# 12_FPGA_MONITOR.net
KiCad netlist of a schematic drawn in Altium Designer
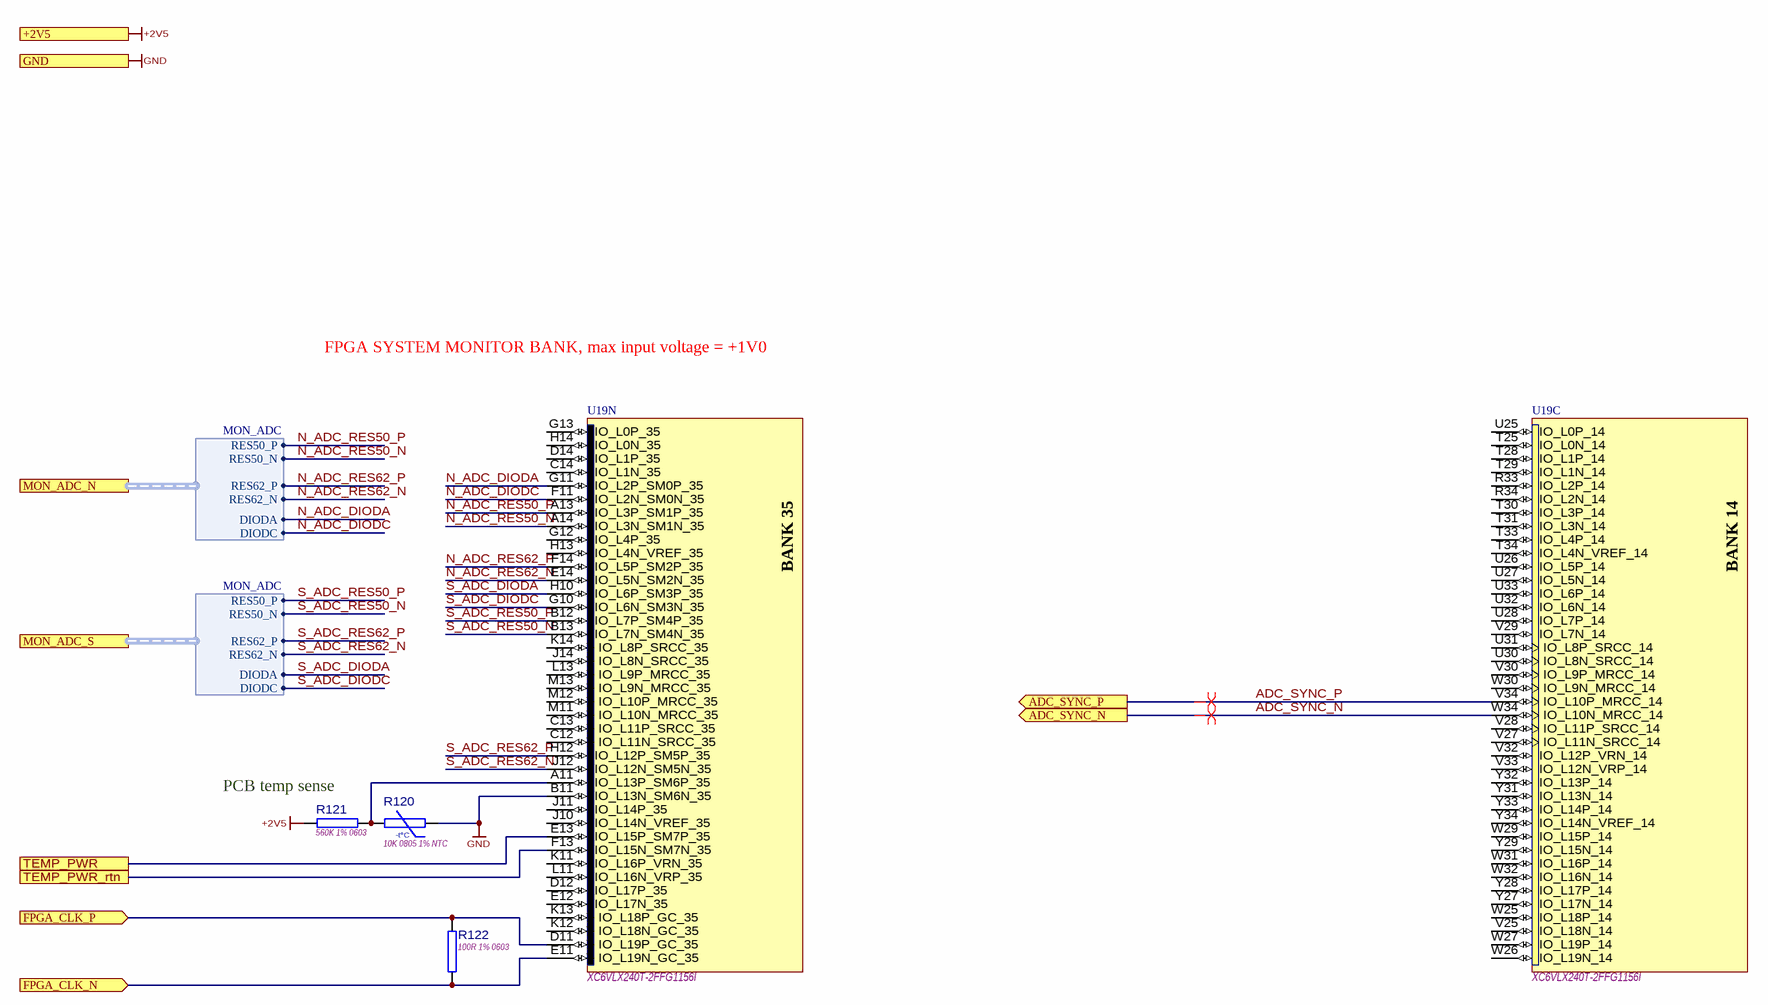
[diagram p0: [12] FPGA_MONITOR.SchDoc]

(export (version "E")
  (design (tool "Eeschema 10.0.6"))
  (components
    (comp (ref "R120")
      (value "10K 0805 1% NTC")
      (footprint "RESC2012N")
      (description "10K NTC resistor 1%  0805 (2012 metric)")
      (fields (field (name "PARTNUMBER") "NTCS0805E3103FLT"))
      (libsource (lib "Omnisys Vault") (part "RES-2PIN-NTC"))
    )
    (comp (ref "R121")
      (value "560K 1% 0603")
      (footprint "RESC1608N")
      (description "Thick film Chip Resistor, 0603/1608")
      (fields (field (name "POWER") "100mW") (field (name "TOLERANCE") "1%"))
      (libsource (lib "Omnisys Vault") (part "RES-2PIN"))
    )
    (comp (ref "R122")
      (value "100R 1% 0603")
      (footprint "RESC1608N")
      (description "Thick film Chip Resistor, 0603/1608")
      (fields (field (name "POWER") "100mW") (field (name "TOLERANCE") "1%"))
      (libsource (lib "Omnisys Vault") (part "RES-2PIN"))
    )
    (comp (ref "U19")
      (value "XC6VLX240T-2FFG1156I")
      (footprint "FFG1156")
      (description "FPGA Virtex-6 LXT Family 241152 Cells 40nm (CMOS) Technology 1V 1156-Pin FCBGA")
      (libsource (lib "Omnisys Vault") (part "FPGA-XVR6-XC6VXXXXXT-GA1156"))
    )
  )
  (nets
    (net (code "2") (name "+2V5") (class "Default")
      (node (ref "R121") (pin "1") (pinfunction "1_1") (pintype "passive"))
    )
    (net (code "3") (name "/ADC_SYNC_N") (class "Default")
      (node (ref "U19") (pin "W34") (pinfunction "IO_L10N_MRCC_14_W34") (pintype "bidirectional"))
    )
    (net (code "4") (name "/ADC_SYNC_P") (class "Default")
      (node (ref "U19") (pin "V34") (pinfunction "IO_L10P_MRCC_14_V34") (pintype "bidirectional"))
    )
    (net (code "5") (name "/FPGA_CLK_N") (class "Default")
      (node (ref "R122") (pin "1") (pinfunction "1_1") (pintype "passive"))
      (node (ref "U19") (pin "E11") (pinfunction "IO_L19N_GC_35_E11") (pintype "bidirectional"))
    )
    (net (code "6") (name "/FPGA_CLK_P") (class "Default")
      (node (ref "R122") (pin "2") (pinfunction "2_2") (pintype "passive"))
      (node (ref "U19") (pin "D11") (pinfunction "IO_L19P_GC_35_D11") (pintype "bidirectional"))
    )
    (net (code "7") (name "/N_ADC_DIODA") (class "Default")
      (node (ref "U19") (pin "G11") (pinfunction "IO_L2P_SM0P_35_G11") (pintype "bidirectional"))
    )
    (net (code "8") (name "/N_ADC_DIODC") (class "Default")
      (node (ref "U19") (pin "F11") (pinfunction "IO_L2N_SM0N_35_F11") (pintype "bidirectional"))
    )
    (net (code "9") (name "/N_ADC_RES50_N") (class "Default")
      (node (ref "U19") (pin "A14") (pinfunction "IO_L3N_SM1N_35_A14") (pintype "bidirectional"))
    )
    (net (code "10") (name "/N_ADC_RES50_P") (class "Default")
      (node (ref "U19") (pin "A13") (pinfunction "IO_L3P_SM1P_35_A13") (pintype "bidirectional"))
    )
    (net (code "11") (name "/N_ADC_RES62_N") (class "Default")
      (node (ref "U19") (pin "E14") (pinfunction "IO_L5N_SM2N_35_E14") (pintype "bidirectional"))
    )
    (net (code "12") (name "/N_ADC_RES62_P") (class "Default")
      (node (ref "U19") (pin "F14") (pinfunction "IO_L5P_SM2P_35_F14") (pintype "bidirectional"))
    )
    (net (code "13") (name "/S_ADC_DIODA") (class "Default")
      (node (ref "U19") (pin "H10") (pinfunction "IO_L6P_SM3P_35_H10") (pintype "bidirectional"))
    )
    (net (code "14") (name "/S_ADC_DIODC") (class "Default")
      (node (ref "U19") (pin "G10") (pinfunction "IO_L6N_SM3N_35_G10") (pintype "bidirectional"))
    )
    (net (code "15") (name "/S_ADC_RES50_N") (class "Default")
      (node (ref "U19") (pin "B13") (pinfunction "IO_L7N_SM4N_35_B13") (pintype "bidirectional"))
    )
    (net (code "16") (name "/S_ADC_RES50_P") (class "Default")
      (node (ref "U19") (pin "B12") (pinfunction "IO_L7P_SM4P_35_B12") (pintype "bidirectional"))
    )
    (net (code "17") (name "/S_ADC_RES62_N") (class "Default")
      (node (ref "U19") (pin "J12") (pinfunction "IO_L12N_SM5N_35_J12") (pintype "bidirectional"))
    )
    (net (code "18") (name "/S_ADC_RES62_P") (class "Default")
      (node (ref "U19") (pin "H12") (pinfunction "IO_L12P_SM5P_35_H12") (pintype "bidirectional"))
    )
    (net (code "19") (name "/TEMP_PWR") (class "Default")
      (node (ref "U19") (pin "E13") (pinfunction "IO_L15P_SM7P_35_E13") (pintype "bidirectional"))
    )
    (net (code "20") (name "/TEMP_PWR_rtn") (class "Default")
      (node (ref "U19") (pin "F13") (pinfunction "IO_L15N_SM7N_35_F13") (pintype "bidirectional"))
    )
    (net (code "22") (name "GND") (class "Default")
      (node (ref "R120") (pin "1") (pinfunction "1_1") (pintype "passive"))
      (node (ref "U19") (pin "B11") (pinfunction "IO_L13N_SM6N_35_B11") (pintype "bidirectional"))
    )
    (net (code "23") (name "Net-(U19N-IO_L13P_SM6P_35)") (class "Default")
      (node (ref "R120") (pin "2") (pinfunction "2_2") (pintype "passive"))
      (node (ref "R121") (pin "2") (pinfunction "2_2") (pintype "passive"))
      (node (ref "U19") (pin "A11") (pinfunction "IO_L13P_SM6P_35_A11") (pintype "bidirectional"))
    )
    (net (code "24") (name "unconnected-(U19C-IO_L0N_14-PadT25)") (class "Default")
      (node (ref "U19") (pin "T25") (pinfunction "IO_L0N_14_T25") (pintype "bidirectional"))
    )
    (net (code "25") (name "unconnected-(U19C-IO_L0P_14-PadU25)") (class "Default")
      (node (ref "U19") (pin "U25") (pinfunction "IO_L0P_14_U25") (pintype "bidirectional"))
    )
    (net (code "26") (name "unconnected-(U19C-IO_L1N_14-PadT29)") (class "Default")
      (node (ref "U19") (pin "T29") (pinfunction "IO_L1N_14_T29") (pintype "bidirectional"))
    )
    (net (code "27") (name "unconnected-(U19C-IO_L1P_14-PadT28)") (class "Default")
      (node (ref "U19") (pin "T28") (pinfunction "IO_L1P_14_T28") (pintype "bidirectional"))
    )
    (net (code "28") (name "unconnected-(U19C-IO_L2N_14-PadR34)") (class "Default")
      (node (ref "U19") (pin "R34") (pinfunction "IO_L2N_14_R34") (pintype "bidirectional"))
    )
    (net (code "29") (name "unconnected-(U19C-IO_L2P_14-PadR33)") (class "Default")
      (node (ref "U19") (pin "R33") (pinfunction "IO_L2P_14_R33") (pintype "bidirectional"))
    )
    (net (code "30") (name "unconnected-(U19C-IO_L3N_14-PadT31)") (class "Default")
      (node (ref "U19") (pin "T31") (pinfunction "IO_L3N_14_T31") (pintype "bidirectional"))
    )
    (net (code "31") (name "unconnected-(U19C-IO_L3P_14-PadT30)") (class "Default")
      (node (ref "U19") (pin "T30") (pinfunction "IO_L3P_14_T30") (pintype "bidirectional"))
    )
    (net (code "32") (name "unconnected-(U19C-IO_L4N_VREF_14-PadT34)") (class "Default")
      (node (ref "U19") (pin "T34") (pinfunction "IO_L4N_VREF_14_T34") (pintype "bidirectional"))
    )
    (net (code "33") (name "unconnected-(U19C-IO_L4P_14-PadT33)") (class "Default")
      (node (ref "U19") (pin "T33") (pinfunction "IO_L4P_14_T33") (pintype "bidirectional"))
    )
    (net (code "34") (name "unconnected-(U19C-IO_L5N_14-PadU27)") (class "Default")
      (node (ref "U19") (pin "U27") (pinfunction "IO_L5N_14_U27") (pintype "bidirectional"))
    )
    (net (code "35") (name "unconnected-(U19C-IO_L5P_14-PadU26)") (class "Default")
      (node (ref "U19") (pin "U26") (pinfunction "IO_L5P_14_U26") (pintype "bidirectional"))
    )
    (net (code "36") (name "unconnected-(U19C-IO_L6N_14-PadU32)") (class "Default")
      (node (ref "U19") (pin "U32") (pinfunction "IO_L6N_14_U32") (pintype "bidirectional"))
    )
    (net (code "37") (name "unconnected-(U19C-IO_L6P_14-PadU33)") (class "Default")
      (node (ref "U19") (pin "U33") (pinfunction "IO_L6P_14_U33") (pintype "bidirectional"))
    )
    (net (code "38") (name "unconnected-(U19C-IO_L7N_14-PadV29)") (class "Default")
      (node (ref "U19") (pin "V29") (pinfunction "IO_L7N_14_V29") (pintype "bidirectional"))
    )
    (net (code "39") (name "unconnected-(U19C-IO_L7P_14-PadU28)") (class "Default")
      (node (ref "U19") (pin "U28") (pinfunction "IO_L7P_14_U28") (pintype "bidirectional"))
    )
    (net (code "40") (name "unconnected-(U19C-IO_L8N_SRCC_14-PadU30)") (class "Default")
      (node (ref "U19") (pin "U30") (pinfunction "IO_L8N_SRCC_14_U30") (pintype "bidirectional"))
    )
    (net (code "41") (name "unconnected-(U19C-IO_L8P_SRCC_14-PadU31)") (class "Default")
      (node (ref "U19") (pin "U31") (pinfunction "IO_L8P_SRCC_14_U31") (pintype "bidirectional"))
    )
    (net (code "42") (name "unconnected-(U19C-IO_L9N_MRCC_14-PadW30)") (class "Default")
      (node (ref "U19") (pin "W30") (pinfunction "IO_L9N_MRCC_14_W30") (pintype "bidirectional"))
    )
    (net (code "43") (name "unconnected-(U19C-IO_L9P_MRCC_14-PadV30)") (class "Default")
      (node (ref "U19") (pin "V30") (pinfunction "IO_L9P_MRCC_14_V30") (pintype "bidirectional"))
    )
    (net (code "44") (name "unconnected-(U19C-IO_L11N_SRCC_14-PadV27)") (class "Default")
      (node (ref "U19") (pin "V27") (pinfunction "IO_L11N_SRCC_14_V27") (pintype "bidirectional"))
    )
    (net (code "45") (name "unconnected-(U19C-IO_L11P_SRCC_14-PadV28)") (class "Default")
      (node (ref "U19") (pin "V28") (pinfunction "IO_L11P_SRCC_14_V28") (pintype "bidirectional"))
    )
    (net (code "46") (name "unconnected-(U19C-IO_L12N_VRP_14-PadV33)") (class "Default")
      (node (ref "U19") (pin "V33") (pinfunction "IO_L12N_VRP_14_V33") (pintype "bidirectional"))
    )
    (net (code "47") (name "unconnected-(U19C-IO_L12P_VRN_14-PadV32)") (class "Default")
      (node (ref "U19") (pin "V32") (pinfunction "IO_L12P_VRN_14_V32") (pintype "bidirectional"))
    )
    (net (code "48") (name "unconnected-(U19C-IO_L13N_14-PadY31)") (class "Default")
      (node (ref "U19") (pin "Y31") (pinfunction "IO_L13N_14_Y31") (pintype "bidirectional"))
    )
    (net (code "49") (name "unconnected-(U19C-IO_L13P_14-PadY32)") (class "Default")
      (node (ref "U19") (pin "Y32") (pinfunction "IO_L13P_14_Y32") (pintype "bidirectional"))
    )
    (net (code "50") (name "unconnected-(U19C-IO_L14N_VREF_14-PadY34)") (class "Default")
      (node (ref "U19") (pin "Y34") (pinfunction "IO_L14N_VREF_14_Y34") (pintype "bidirectional"))
    )
    (net (code "51") (name "unconnected-(U19C-IO_L14P_14-PadY33)") (class "Default")
      (node (ref "U19") (pin "Y33") (pinfunction "IO_L14P_14_Y33") (pintype "bidirectional"))
    )
    (net (code "52") (name "unconnected-(U19C-IO_L15N_14-PadY29)") (class "Default")
      (node (ref "U19") (pin "Y29") (pinfunction "IO_L15N_14_Y29") (pintype "bidirectional"))
    )
    (net (code "53") (name "unconnected-(U19C-IO_L15P_14-PadW29)") (class "Default")
      (node (ref "U19") (pin "W29") (pinfunction "IO_L15P_14_W29") (pintype "bidirectional"))
    )
    (net (code "54") (name "unconnected-(U19C-IO_L16N_14-PadW32)") (class "Default")
      (node (ref "U19") (pin "W32") (pinfunction "IO_L16N_14_W32") (pintype "bidirectional"))
    )
    (net (code "55") (name "unconnected-(U19C-IO_L16P_14-PadW31)") (class "Default")
      (node (ref "U19") (pin "W31") (pinfunction "IO_L16P_14_W31") (pintype "bidirectional"))
    )
    (net (code "56") (name "unconnected-(U19C-IO_L17N_14-PadY27)") (class "Default")
      (node (ref "U19") (pin "Y27") (pinfunction "IO_L17N_14_Y27") (pintype "bidirectional"))
    )
    (net (code "57") (name "unconnected-(U19C-IO_L17P_14-PadY28)") (class "Default")
      (node (ref "U19") (pin "Y28") (pinfunction "IO_L17P_14_Y28") (pintype "bidirectional"))
    )
    (net (code "58") (name "unconnected-(U19C-IO_L18N_14-PadV25)") (class "Default")
      (node (ref "U19") (pin "V25") (pinfunction "IO_L18N_14_V25") (pintype "bidirectional"))
    )
    (net (code "59") (name "unconnected-(U19C-IO_L18P_14-PadW25)") (class "Default")
      (node (ref "U19") (pin "W25") (pinfunction "IO_L18P_14_W25") (pintype "bidirectional"))
    )
    (net (code "60") (name "unconnected-(U19C-IO_L19N_14-PadW26)") (class "Default")
      (node (ref "U19") (pin "W26") (pinfunction "IO_L19N_14_W26") (pintype "bidirectional"))
    )
    (net (code "61") (name "unconnected-(U19C-IO_L19P_14-PadW27)") (class "Default")
      (node (ref "U19") (pin "W27") (pinfunction "IO_L19P_14_W27") (pintype "bidirectional"))
    )
    (net (code "62") (name "unconnected-(U19N-IO_L0N_35-PadH14)") (class "Default")
      (node (ref "U19") (pin "H14") (pinfunction "IO_L0N_35_H14") (pintype "bidirectional"))
    )
    (net (code "63") (name "unconnected-(U19N-IO_L0P_35-PadG13)") (class "Default")
      (node (ref "U19") (pin "G13") (pinfunction "IO_L0P_35_G13") (pintype "bidirectional"))
    )
    (net (code "64") (name "unconnected-(U19N-IO_L1N_35-PadC14)") (class "Default")
      (node (ref "U19") (pin "C14") (pinfunction "IO_L1N_35_C14") (pintype "bidirectional"))
    )
    (net (code "65") (name "unconnected-(U19N-IO_L1P_35-PadD14)") (class "Default")
      (node (ref "U19") (pin "D14") (pinfunction "IO_L1P_35_D14") (pintype "bidirectional"))
    )
    (net (code "66") (name "unconnected-(U19N-IO_L4N_VREF_35-PadH13)") (class "Default")
      (node (ref "U19") (pin "H13") (pinfunction "IO_L4N_VREF_35_H13") (pintype "bidirectional"))
    )
    (net (code "67") (name "unconnected-(U19N-IO_L4P_35-PadG12)") (class "Default")
      (node (ref "U19") (pin "G12") (pinfunction "IO_L4P_35_G12") (pintype "bidirectional"))
    )
    (net (code "68") (name "unconnected-(U19N-IO_L8N_SRCC_35-PadJ14)") (class "Default")
      (node (ref "U19") (pin "J14") (pinfunction "IO_L8N_SRCC_35_J14") (pintype "bidirectional"))
    )
    (net (code "69") (name "unconnected-(U19N-IO_L8P_SRCC_35-PadK14)") (class "Default")
      (node (ref "U19") (pin "K14") (pinfunction "IO_L8P_SRCC_35_K14") (pintype "bidirectional"))
    )
    (net (code "70") (name "unconnected-(U19N-IO_L9N_MRCC_35-PadM13)") (class "Default")
      (node (ref "U19") (pin "M13") (pinfunction "IO_L9N_MRCC_35_M13") (pintype "bidirectional"))
    )
    (net (code "71") (name "unconnected-(U19N-IO_L9P_MRCC_35-PadL13)") (class "Default")
      (node (ref "U19") (pin "L13") (pinfunction "IO_L9P_MRCC_35_L13") (pintype "bidirectional"))
    )
    (net (code "72") (name "unconnected-(U19N-IO_L10N_MRCC_35-PadM11)") (class "Default")
      (node (ref "U19") (pin "M11") (pinfunction "IO_L10N_MRCC_35_M11") (pintype "bidirectional"))
    )
    (net (code "73") (name "unconnected-(U19N-IO_L10P_MRCC_35-PadM12)") (class "Default")
      (node (ref "U19") (pin "M12") (pinfunction "IO_L10P_MRCC_35_M12") (pintype "bidirectional"))
    )
    (net (code "74") (name "unconnected-(U19N-IO_L11N_SRCC_35-PadC12)") (class "Default")
      (node (ref "U19") (pin "C12") (pinfunction "IO_L11N_SRCC_35_C12") (pintype "bidirectional"))
    )
    (net (code "75") (name "unconnected-(U19N-IO_L11P_SRCC_35-PadC13)") (class "Default")
      (node (ref "U19") (pin "C13") (pinfunction "IO_L11P_SRCC_35_C13") (pintype "bidirectional"))
    )
    (net (code "76") (name "unconnected-(U19N-IO_L14N_VREF_35-PadJ10)") (class "Default")
      (node (ref "U19") (pin "J10") (pinfunction "IO_L14N_VREF_35_J10") (pintype "bidirectional"))
    )
    (net (code "77") (name "unconnected-(U19N-IO_L14P_35-PadJ11)") (class "Default")
      (node (ref "U19") (pin "J11") (pinfunction "IO_L14P_35_J11") (pintype "bidirectional"))
    )
    (net (code "78") (name "unconnected-(U19N-IO_L16N_VRP_35-PadL11)") (class "Default")
      (node (ref "U19") (pin "L11") (pinfunction "IO_L16N_VRP_35_L11") (pintype "bidirectional"))
    )
    (net (code "79") (name "unconnected-(U19N-IO_L16P_VRN_35-PadK11)") (class "Default")
      (node (ref "U19") (pin "K11") (pinfunction "IO_L16P_VRN_35_K11") (pintype "bidirectional"))
    )
    (net (code "80") (name "unconnected-(U19N-IO_L17N_35-PadE12)") (class "Default")
      (node (ref "U19") (pin "E12") (pinfunction "IO_L17N_35_E12") (pintype "bidirectional"))
    )
    (net (code "81") (name "unconnected-(U19N-IO_L17P_35-PadD12)") (class "Default")
      (node (ref "U19") (pin "D12") (pinfunction "IO_L17P_35_D12") (pintype "bidirectional"))
    )
    (net (code "82") (name "unconnected-(U19N-IO_L18N_GC_35-PadK12)") (class "Default")
      (node (ref "U19") (pin "K12") (pinfunction "IO_L18N_GC_35_K12") (pintype "bidirectional"))
    )
    (net (code "83") (name "unconnected-(U19N-IO_L18P_GC_35-PadK13)") (class "Default")
      (node (ref "U19") (pin "K13") (pinfunction "IO_L18P_GC_35_K13") (pintype "bidirectional"))
    )
  )
)
